# InkTime.net
KiCad netlist of a schematic drawn in EAGLE
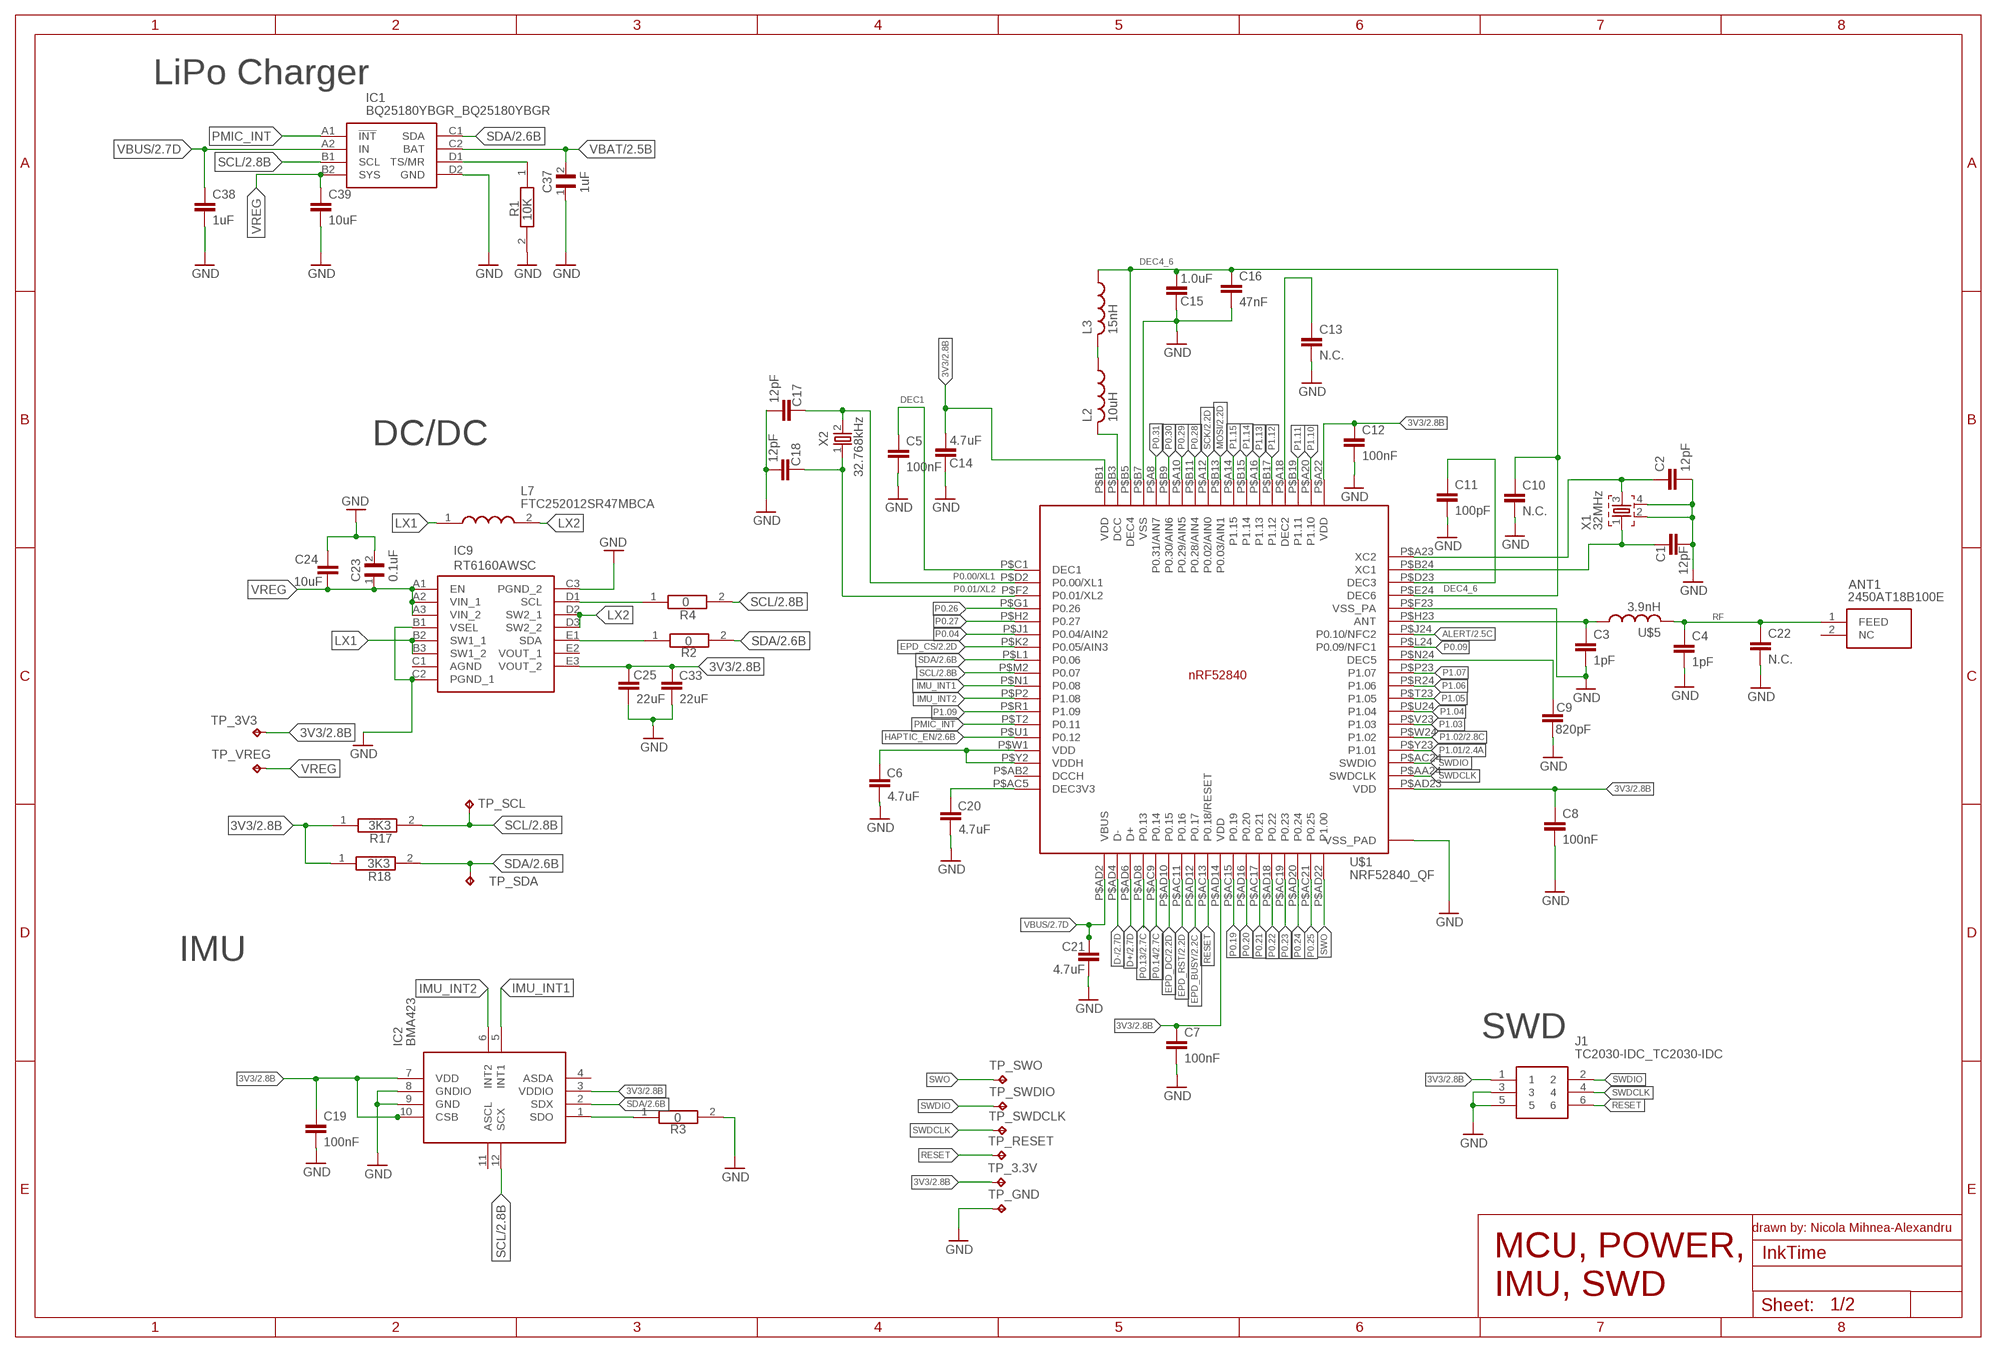
[diagram p0: schematic, sheet 1]
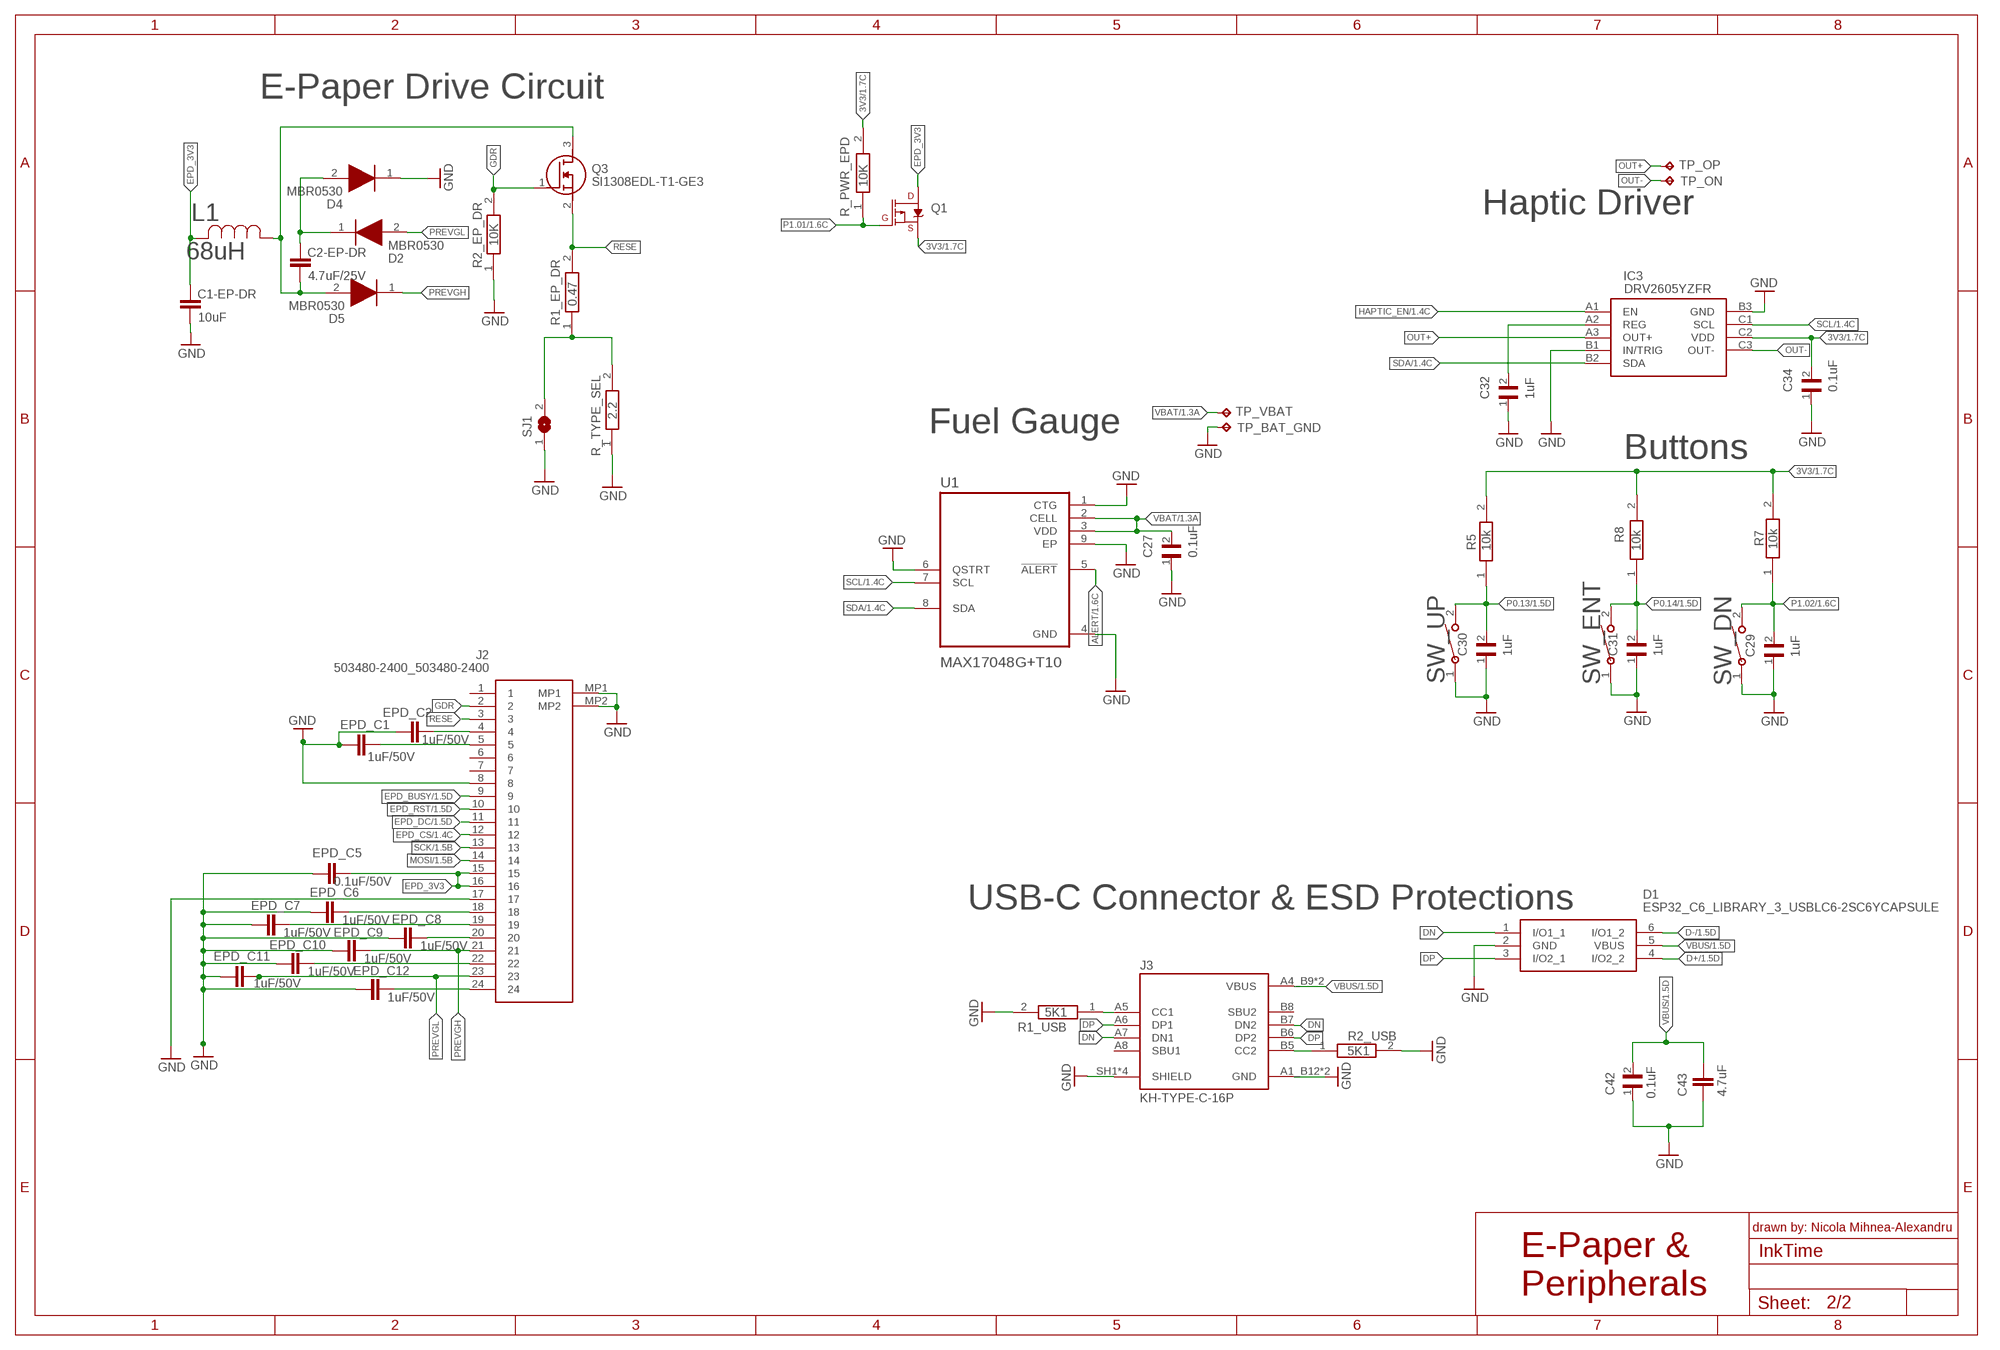
[diagram p1: schematic, sheet 2]

(export (version "E")
  (design (tool "Eeschema 10.0.6"))
  (components
    (comp (ref "C1-EP-DR")
      (value "10uF")
      (footprint "eagle-import:NORDIC_NRF_3_RESC0402_N")
      (libsource (lib "eagle-import") (part "NORDIC_NRF_3_CAPACITOR_0402_N"))
    )
    (comp (ref "C2-EP-DR")
      (value "4.7uF/25V")
      (footprint "eagle-import:NORDIC_NRF_3_RESC0402_N")
      (libsource (lib "eagle-import") (part "NORDIC_NRF_3_CAPACITOR_0402_N"))
    )
    (comp (ref "C27")
      (value "0.1uF")
      (footprint "eagle-import:GRM011R60J152KE01L_2_CAPC0201X13N")
      (libsource (lib "eagle-import") (part "GRM011R60J152KE01L_2_GRM011R60J152KE01LGRM"))
    )
    (comp (ref "C29")
      (value "1uF")
      (footprint "eagle-import:GRM011R60J152KE01L_2_CAPC0201X13N")
      (libsource (lib "eagle-import") (part "GRM011R60J152KE01L_2_GRM011R60J152KE01LGRM"))
    )
    (comp (ref "C30")
      (value "1uF")
      (footprint "eagle-import:GRM011R60J152KE01L_2_CAPC0201X13N")
      (libsource (lib "eagle-import") (part "GRM011R60J152KE01L_2_GRM011R60J152KE01LGRM"))
    )
    (comp (ref "C31")
      (value "1uF")
      (footprint "eagle-import:GRM011R60J152KE01L_2_CAPC0201X13N")
      (libsource (lib "eagle-import") (part "GRM011R60J152KE01L_2_GRM011R60J152KE01LGRM"))
    )
    (comp (ref "C32")
      (value "1uF")
      (footprint "eagle-import:GRM011R60J152KE01L_2_CAPC0201X13N")
      (libsource (lib "eagle-import") (part "GRM011R60J152KE01L_2_GRM011R60J152KE01LGRM"))
    )
    (comp (ref "C34")
      (value "0.1uF")
      (footprint "eagle-import:GRM011R60J152KE01L_2_CAPC0201X13N")
      (libsource (lib "eagle-import") (part "GRM011R60J152KE01L_2_GRM011R60J152KE01LGRM"))
    )
    (comp (ref "C42")
      (value "0.1uF")
      (footprint "eagle-import:GRM011R60J152KE01L_2_CAPC0201X13N")
      (fields (field (name "MF") "Murata") (field (name "MP") "GRM011R60J152KE01L"))
      (libsource (lib "eagle-import") (part "GRM011R60J152KE01L_2_GRM011R60J152KE01L"))
    )
    (comp (ref "C43")
      (value "4.7uF")
      (footprint "eagle-import:NORDIC_NRF_3_RESC0402_N")
      (libsource (lib "eagle-import") (part "NORDIC_NRF_3_CAPACITOR_0402_N"))
    )
    (comp (ref "D1")
      (value "ESP32_C6_LIBRARY_3_USBLC6-2SC6YCAPSULE")
      (footprint "eagle-import:ESP32_C6_LIBRARY_3_SOT95P280X145-6N")
      (libsource (lib "eagle-import") (part "ESP32_C6_LIBRARY_3_USBLC6-2SC6YCAPSULE"))
    )
    (comp (ref "D2")
      (value "MBR0530")
      (footprint "eagle-import:ESP32_C6_LIBRARY_5_SOD3716X135N")
      (libsource (lib "eagle-import") (part "ESP32_C6_LIBRARY_5_MBR0530MBRR"))
    )
    (comp (ref "D4")
      (value "MBR0530")
      (footprint "eagle-import:ESP32_C6_LIBRARY_5_SOD3716X135N")
      (libsource (lib "eagle-import") (part "ESP32_C6_LIBRARY_5_MBR0530MBRR"))
    )
    (comp (ref "D5")
      (value "MBR0530")
      (footprint "eagle-import:ESP32_C6_LIBRARY_5_SOD3716X135N")
      (libsource (lib "eagle-import") (part "ESP32_C6_LIBRARY_5_MBR0530MBRR"))
    )
    (comp (ref "EPD_C1")
      (value "1uF/50V")
      (footprint "eagle-import:NORDIC_NRF_3_RESC0402_N")
      (libsource (lib "eagle-import") (part "NORDIC_NRF_3_CAPACITOR_0402_N"))
    )
    (comp (ref "EPD_C2")
      (value "1uF/50V")
      (footprint "eagle-import:NORDIC_NRF_3_RESC0402_N")
      (libsource (lib "eagle-import") (part "NORDIC_NRF_3_CAPACITOR_0402_N"))
    )
    (comp (ref "EPD_C5")
      (value "0.1uF/50V")
      (footprint "eagle-import:NORDIC_NRF_3_RESC0402_N")
      (libsource (lib "eagle-import") (part "NORDIC_NRF_3_CAPACITOR_0402_N"))
    )
    (comp (ref "EPD_C6")
      (value "1uF/50V")
      (footprint "eagle-import:NORDIC_NRF_3_RESC0402_N")
      (libsource (lib "eagle-import") (part "NORDIC_NRF_3_CAPACITOR_0402_N"))
    )
    (comp (ref "EPD_C7")
      (value "1uF/50V")
      (footprint "eagle-import:NORDIC_NRF_3_RESC0402_N")
      (libsource (lib "eagle-import") (part "NORDIC_NRF_3_CAPACITOR_0402_N"))
    )
    (comp (ref "EPD_C8")
      (value "1uF/50V")
      (footprint "eagle-import:NORDIC_NRF_3_RESC0402_N")
      (libsource (lib "eagle-import") (part "NORDIC_NRF_3_CAPACITOR_0402_N"))
    )
    (comp (ref "EPD_C9")
      (value "1uF/50V")
      (footprint "eagle-import:NORDIC_NRF_3_RESC0402_N")
      (libsource (lib "eagle-import") (part "NORDIC_NRF_3_CAPACITOR_0402_N"))
    )
    (comp (ref "EPD_C10")
      (value "1uF/50V")
      (footprint "eagle-import:NORDIC_NRF_3_RESC0402_N")
      (libsource (lib "eagle-import") (part "NORDIC_NRF_3_CAPACITOR_0402_N"))
    )
    (comp (ref "EPD_C11")
      (value "1uF/50V")
      (footprint "eagle-import:NORDIC_NRF_3_RESC0402_N")
      (libsource (lib "eagle-import") (part "NORDIC_NRF_3_CAPACITOR_0402_N"))
    )
    (comp (ref "EPD_C12")
      (value "1uF/50V")
      (footprint "eagle-import:NORDIC_NRF_3_RESC0402_N")
      (libsource (lib "eagle-import") (part "NORDIC_NRF_3_CAPACITOR_0402_N"))
    )
    (comp (ref "IC3")
      (value "DRV2605YZFR")
      (footprint "eagle-import:DRV2605YZFR_BGA9C50P3X3_144X144X62")
      (libsource (lib "eagle-import") (part "DRV2605YZFR_DRV2605YZFR"))
    )
    (comp (ref "J2")
      (value "503480-2400_503480-2400")
      (footprint "eagle-import:503480-2400_5034802400")
      (fields
        (field (name "MANUFACTURER_PART_NUMBER") "503480-2400")
        (field (name "MOUSER_PART_NUMBER") "538-503480-2400")
      )
      (libsource (lib "eagle-import") (part "503480-2400_503480-2400"))
    )
    (comp (ref "J3")
      (value "KH-TYPE-C-16P")
      (footprint "eagle-import:KH-TYPE-C-16P_KINGHELM_KH-TYPE-C-16P")
      (libsource (lib "eagle-import") (part "KH-TYPE-C-16P_KH-TYPE-C-16PKH"))
    )
    (comp (ref "L1")
      (value "68uH")
      (footprint "eagle-import:ESP32_C6_LIBRARY_2_IND_4828-WE-TPC_WRE")
      (fields
        (field (name "MANUFACTURER_PART_NUMBER") "744043680")
        (field (name "COPYRIGHT") "Copyright (C) 2024 Ultra Librarian. All rights reserved.")
      )
      (libsource (lib "eagle-import") (part "ESP32_C6_LIBRARY_2_744043680IND_4828-WE-TPC_WRE"))
    )
    (comp (ref "Q1")
      (value "ESP32_C6_LIBRARY_4_ESP32_WROVER_SPARKFUN-DISCRETESEMI_MOSFET_PCH")
      (footprint "eagle-import:ESP32_C6_LIBRARY_4_ESP32_C6_LIBRARY_4_ESP32_C6_LIBRARY_4_ESP32_C6_LIBRARY_4_ESP32_WROVER_SPARKFUN-DISCRETESEMI_SOT23-3")
      (libsource (lib "eagle-import") (part "ESP32_C6_LIBRARY_4_ESP32_WROVER_SPARKFUN-DISCRETESEMI_MOSFET_PCH"))
    )
    (comp (ref "Q3")
      (value "SI1308EDL-T1-GE3")
      (footprint "eagle-import:ESP32_C6_LIBRARY_6_SOT65P210X110-3N")
      (libsource (lib "eagle-import") (part "ESP32_C6_LIBRARY_6_SI1308EDL-T1-GE3SIU"))
    )
    (comp (ref "R1_EP_DR")
      (value "0.47")
      (footprint "eagle-import:CPF0201D7K68C1_0201")
      (libsource (lib "eagle-import") (part "CPF0201D7K68C1_CPF0201D7K68C1"))
    )
    (comp (ref "R1_USB")
      (value "5K1")
      (footprint "eagle-import:CPF0201D7K68C1_0201")
      (libsource (lib "eagle-import") (part "CPF0201D7K68C1_CPF0201D7K68C1"))
    )
    (comp (ref "R2_EP_DR")
      (value "10K")
      (footprint "eagle-import:CPF0201D7K68C1_0201")
      (libsource (lib "eagle-import") (part "CPF0201D7K68C1_CPF0201D7K68C1"))
    )
    (comp (ref "R2_USB")
      (value "5K1")
      (footprint "eagle-import:CPF0201D7K68C1_0201")
      (libsource (lib "eagle-import") (part "CPF0201D7K68C1_CPF0201D7K68C1"))
    )
    (comp (ref "R5")
      (value "10k")
      (footprint "eagle-import:CPF0201D7K68C1_0201")
      (libsource (lib "eagle-import") (part "CPF0201D7K68C1_CPF0201D7K68C1"))
    )
    (comp (ref "R7")
      (value "10k")
      (footprint "eagle-import:CPF0201D7K68C1_0201")
      (libsource (lib "eagle-import") (part "CPF0201D7K68C1_CPF0201D7K68C1"))
    )
    (comp (ref "R8")
      (value "10k")
      (footprint "eagle-import:CPF0201D7K68C1_0201")
      (libsource (lib "eagle-import") (part "CPF0201D7K68C1_CPF0201D7K68C1"))
    )
    (comp (ref "R_PWR_EPD")
      (value "10K")
      (footprint "eagle-import:CPF0201D7K68C1_0201")
      (libsource (lib "eagle-import") (part "CPF0201D7K68C1_CPF0201D7K68C1"))
    )
    (comp (ref "R_TYPE_SEL")
      (value "2.2")
      (footprint "eagle-import:CPF0201D7K68C1_0201")
      (libsource (lib "eagle-import") (part "CPF0201D7K68C1_CPF0201D7K68C1"))
    )
    (comp (ref "SJ1")
      (value "ESP32_C6_LIBRARY_7_JUMPER_SJ")
      (footprint "eagle-import:ESP32_C6_LIBRARY_7_JUMPER_SJ")
      (libsource (lib "eagle-import") (part "ESP32_C6_LIBRARY_7_JUMPER_SJ"))
    )
    (comp (ref "SW_DN")
      (value "2025-10-22_07-23-44_LIBRARY_EVP-AKE31A")
      (footprint "eagle-import:2025-10-22_07-23-44_LIBRARY_SW_EVP-AKE31A_PAN")
      (libsource (lib "eagle-import") (part "2025-10-22_07-23-44_LIBRARY_EVP-AKE31A"))
    )
    (comp (ref "SW_ENT")
      (value "2025-10-22_07-23-44_LIBRARY_EVP-AKE31A")
      (footprint "eagle-import:2025-10-22_07-23-44_LIBRARY_SW_EVP-AKE31A_PAN")
      (libsource (lib "eagle-import") (part "2025-10-22_07-23-44_LIBRARY_EVP-AKE31A"))
    )
    (comp (ref "SW_UP")
      (value "2025-10-22_07-23-44_LIBRARY_EVP-AKE31A")
      (footprint "eagle-import:2025-10-22_07-23-44_LIBRARY_SW_EVP-AKE31A_PAN")
      (libsource (lib "eagle-import") (part "2025-10-22_07-23-44_LIBRARY_EVP-AKE31A"))
    )
    (comp (ref "TP_BAT_GND")
      (value "HECTOR_WATCH_1_TPTP20R")
      (footprint "eagle-import:HECTOR_WATCH_1_TP20R")
      (libsource (lib "eagle-import") (part "HECTOR_WATCH_1_TPTP20R"))
    )
    (comp (ref "TP_ON")
      (value "HECTOR_WATCH_1_TPTP20R")
      (footprint "eagle-import:HECTOR_WATCH_1_TP20R")
      (libsource (lib "eagle-import") (part "HECTOR_WATCH_1_TPTP20R"))
    )
    (comp (ref "TP_OP")
      (value "HECTOR_WATCH_1_TPTP20R")
      (footprint "eagle-import:HECTOR_WATCH_1_TP20R")
      (libsource (lib "eagle-import") (part "HECTOR_WATCH_1_TPTP20R"))
    )
    (comp (ref "TP_VBAT")
      (value "HECTOR_WATCH_1_TPTP20R")
      (footprint "eagle-import:HECTOR_WATCH_1_TP20R")
      (libsource (lib "eagle-import") (part "HECTOR_WATCH_1_TPTP20R"))
    )
    (comp (ref "U1")
      (value "MAX17048G+T10")
      (footprint "eagle-import:ESP32_C6_LIBRARY_SON50P200X200X80-9N")
      (fields (field (name "MF") "Analog Devices"))
      (libsource (lib "eagle-import") (part "ESP32_C6_LIBRARY_MAX17048G+T10"))
    )
    (comp (ref "ANT1")
      (value "2450AT18B100E")
      (footprint "eagle-import:2450AT18B100E_ANTC3216X140N")
      (fields (field (name "MOUSER_PART_NUMBER") "609-2450AT18B100E"))
      (libsource (lib "eagle-import") (part "2450AT18B100E_2450AT18B100E"))
    )
    (comp (ref "C1")
      (value "12pF")
      (footprint "eagle-import:NORDIC_NRF_3_RESC0201_N")
      (libsource (lib "eagle-import") (part "NORDIC_NRF_3_CAPACITOR_0201_N"))
    )
    (comp (ref "C2")
      (value "12pF")
      (footprint "eagle-import:NORDIC_NRF_3_RESC0201_N")
      (libsource (lib "eagle-import") (part "NORDIC_NRF_3_CAPACITOR_0201_N"))
    )
    (comp (ref "C3")
      (value "1pF")
      (footprint "eagle-import:NORDIC_NRF_3_RESC0201_N")
      (libsource (lib "eagle-import") (part "NORDIC_NRF_3_CAPACITOR_0201_N"))
    )
    (comp (ref "C4")
      (value "1pF")
      (footprint "eagle-import:NORDIC_NRF_3_RESC0201_N")
      (libsource (lib "eagle-import") (part "NORDIC_NRF_3_CAPACITOR_0201_N"))
    )
    (comp (ref "C5")
      (value "100nF")
      (footprint "eagle-import:NORDIC_NRF_3_RESC0201_N")
      (libsource (lib "eagle-import") (part "NORDIC_NRF_3_CAPACITOR_0201_N"))
    )
    (comp (ref "C6")
      (value "4.7uF")
      (footprint "eagle-import:NORDIC_NRF_3_RESC0402_N")
      (libsource (lib "eagle-import") (part "NORDIC_NRF_3_CAPACITOR_0402_N"))
    )
    (comp (ref "C7")
      (value "100nF")
      (footprint "eagle-import:NORDIC_NRF_3_RESC0201_N")
      (libsource (lib "eagle-import") (part "NORDIC_NRF_3_CAPACITOR_0201_N"))
    )
    (comp (ref "C8")
      (value "100nF")
      (footprint "eagle-import:NORDIC_NRF_3_RESC0201_N")
      (libsource (lib "eagle-import") (part "NORDIC_NRF_3_CAPACITOR_0201_N"))
    )
    (comp (ref "C9")
      (value "820pF")
      (footprint "eagle-import:NORDIC_NRF_3_RESC0201_N")
      (libsource (lib "eagle-import") (part "NORDIC_NRF_3_CAPACITOR_0201_N"))
    )
    (comp (ref "C10")
      (value "N.C.")
      (footprint "eagle-import:NORDIC_NRF_3_RESC0201_N")
      (libsource (lib "eagle-import") (part "NORDIC_NRF_3_CAPACITOR_0201_N"))
    )
    (comp (ref "C11")
      (value "100pF")
      (footprint "eagle-import:NORDIC_NRF_3_RESC0201_N")
      (libsource (lib "eagle-import") (part "NORDIC_NRF_3_CAPACITOR_0201_N"))
    )
    (comp (ref "C12")
      (value "100nF")
      (footprint "eagle-import:NORDIC_NRF_3_RESC0201_N")
      (libsource (lib "eagle-import") (part "NORDIC_NRF_3_CAPACITOR_0201_N"))
    )
    (comp (ref "C13")
      (value "N.C.")
      (footprint "eagle-import:NORDIC_NRF_3_RESC0201_N")
      (libsource (lib "eagle-import") (part "NORDIC_NRF_3_CAPACITOR_0201_N"))
    )
    (comp (ref "C14")
      (value "4.7uF")
      (footprint "eagle-import:NORDIC_NRF_3_RESC0402_N")
      (libsource (lib "eagle-import") (part "NORDIC_NRF_3_CAPACITOR_0402_N"))
    )
    (comp (ref "C15")
      (value "1.0uF")
      (footprint "eagle-import:NORDIC_NRF_3_RESC0402_N")
      (libsource (lib "eagle-import") (part "NORDIC_NRF_3_CAPACITOR_0402_N"))
    )
    (comp (ref "C16")
      (value "47nF")
      (footprint "eagle-import:NORDIC_NRF_3_RESC0201_N")
      (libsource (lib "eagle-import") (part "NORDIC_NRF_3_CAPACITOR_0201_N"))
    )
    (comp (ref "C17")
      (value "12pF")
      (footprint "eagle-import:NORDIC_NRF_3_RESC0201_N")
      (libsource (lib "eagle-import") (part "NORDIC_NRF_3_CAPACITOR_0201_N"))
    )
    (comp (ref "C18")
      (value "12pF")
      (footprint "eagle-import:NORDIC_NRF_3_RESC0201_N")
      (libsource (lib "eagle-import") (part "NORDIC_NRF_3_CAPACITOR_0201_N"))
    )
    (comp (ref "C19")
      (value "100nF")
      (footprint "eagle-import:NORDIC_NRF_3_RESC0201_N")
      (libsource (lib "eagle-import") (part "NORDIC_NRF_3_CAPACITOR_0201_N"))
    )
    (comp (ref "C20")
      (value "4.7uF")
      (footprint "eagle-import:NORDIC_NRF_3_RESC0402_N")
      (libsource (lib "eagle-import") (part "NORDIC_NRF_3_CAPACITOR_0402_N"))
    )
    (comp (ref "C21")
      (value "4.7uF")
      (footprint "eagle-import:NORDIC_NRF_3_RESC0402_N")
      (libsource (lib "eagle-import") (part "NORDIC_NRF_3_CAPACITOR_0402_N"))
    )
    (comp (ref "C22")
      (value "N.C.")
      (footprint "eagle-import:NORDIC_NRF_3_RESC0201_N")
      (libsource (lib "eagle-import") (part "NORDIC_NRF_3_CAPACITOR_0201_N"))
    )
    (comp (ref "C23")
      (value "0.1uF")
      (footprint "eagle-import:GRM011R60J152KE01L_2_CAPC0201X13N")
      (libsource (lib "eagle-import") (part "GRM011R60J152KE01L_2_GRM011R60J152KE01LGRM"))
    )
    (comp (ref "C24")
      (value "10uF")
      (footprint "eagle-import:NORDIC_NRF_3_RESC0402_N")
      (libsource (lib "eagle-import") (part "NORDIC_NRF_3_CAPACITOR_0402_N"))
    )
    (comp (ref "C25")
      (value "22uF")
      (footprint "eagle-import:NORDIC_NRF_3_RESC0402_N")
      (libsource (lib "eagle-import") (part "NORDIC_NRF_3_CAPACITOR_0402_N"))
    )
    (comp (ref "C33")
      (value "22uF")
      (footprint "eagle-import:NORDIC_NRF_3_RESC0402_N")
      (libsource (lib "eagle-import") (part "NORDIC_NRF_3_CAPACITOR_0402_N"))
    )
    (comp (ref "C37")
      (value "1uF")
      (footprint "eagle-import:GRM011R60J152KE01L_2_CAPC0201X13N")
      (libsource (lib "eagle-import") (part "GRM011R60J152KE01L_2_GRM011R60J152KE01LGRM"))
    )
    (comp (ref "C38")
      (value "1uF")
      (footprint "eagle-import:NORDIC_NRF_3_RESC0402_N")
      (libsource (lib "eagle-import") (part "NORDIC_NRF_3_CAPACITOR_0402_N"))
    )
    (comp (ref "C39")
      (value "10uF")
      (footprint "eagle-import:NORDIC_NRF_3_RESC0402_N")
      (libsource (lib "eagle-import") (part "NORDIC_NRF_3_CAPACITOR_0402_N"))
    )
    (comp (ref "IC1")
      (value "BQ25180YBGR_BQ25180YBGR")
      (footprint "eagle-import:BQ25180YBGR_BGA8C40P2X4_100X155X50")
      (fields
        (field (name "ARROW_PART_NUMBER") "BQ25180YBGR")
        (field (name "MOUSER_PART_NUMBER") "595-BQ25180YBGR")
      )
      (libsource (lib "eagle-import") (part "BQ25180YBGR_BQ25180YBGR"))
    )
    (comp (ref "IC2")
      (value "BMA423")
      (footprint "eagle-import:BMA423_BMA423")
      (fields (field (name "MOUSER_PART_NUMBER") "262-BMA423"))
      (libsource (lib "eagle-import") (part "BMA423_BMA423"))
    )
    (comp (ref "IC9")
      (value "RT6160AWSC")
      (footprint "eagle-import:RT6160AWSC_BGA15C40P3X5_140X230X60")
      (fields (field (name "MOUSER_PART_NUMBER") "835-RT6160AWSC"))
      (libsource (lib "eagle-import") (part "RT6160AWSC_RT6160AWSC"))
    )
    (comp (ref "J1")
      (value "TC2030-IDC_TC2030-IDC")
      (footprint "eagle-import:TC2030-IDC_TC2030IDC")
      (fields (field (name "MANUFACTURER_PART_NUMBER") "TC2030-IDC"))
      (libsource (lib "eagle-import") (part "TC2030-IDC_TC2030-IDC"))
    )
    (comp (ref "L2")
      (value "10uH")
      (footprint "eagle-import:NORDIC_NRF_2_RESC0201_N")
      (libsource (lib "eagle-import") (part "NORDIC_NRF_2_INDUCTOR_0201_N"))
    )
    (comp (ref "L3")
      (value "15nH")
      (footprint "eagle-import:NORDIC_NRF_2_RESC0201_N")
      (libsource (lib "eagle-import") (part "NORDIC_NRF_2_INDUCTOR_0201_N"))
    )
    (comp (ref "L7")
      (value "FTC252012SR47MBCA")
      (footprint "eagle-import:MLP2016SR47MT0S1_INDC2016X100N")
      (libsource (lib "eagle-import") (part "MLP2016SR47MT0S1_FTC252012SR47MBCA"))
    )
    (comp (ref "R1")
      (value "10K")
      (footprint "eagle-import:CPF0201D7K68C1_0201")
      (libsource (lib "eagle-import") (part "CPF0201D7K68C1_CPF0201D7K68C1"))
    )
    (comp (ref "R2")
      (value "0")
      (footprint "eagle-import:CPF0201D7K68C1_0201")
      (libsource (lib "eagle-import") (part "CPF0201D7K68C1_CPF0201D7K68C1"))
    )
    (comp (ref "R3")
      (value "0")
      (footprint "eagle-import:CPF0201D7K68C1_0201")
      (libsource (lib "eagle-import") (part "CPF0201D7K68C1_CPF0201D7K68C1"))
    )
    (comp (ref "R4")
      (value "0")
      (footprint "eagle-import:CPF0201D7K68C1_0201")
      (libsource (lib "eagle-import") (part "CPF0201D7K68C1_CPF0201D7K68C1"))
    )
    (comp (ref "R17")
      (value "3K3")
      (footprint "eagle-import:CPF0201D7K68C1_0201")
      (libsource (lib "eagle-import") (part "CPF0201D7K68C1_CPF0201D7K68C1"))
    )
    (comp (ref "R18")
      (value "3K3")
      (footprint "eagle-import:CPF0201D7K68C1_0201")
      (libsource (lib "eagle-import") (part "CPF0201D7K68C1_CPF0201D7K68C1"))
    )
    (comp (ref "TP_3.3V")
      (value "HECTOR_WATCH_1_TPTP20R")
      (footprint "eagle-import:HECTOR_WATCH_1_TP20R")
      (libsource (lib "eagle-import") (part "HECTOR_WATCH_1_TPTP20R"))
    )
    (comp (ref "TP_3V3")
      (value "HECTOR_WATCH_1_TPTP20R")
      (footprint "eagle-import:HECTOR_WATCH_1_TP20R")
      (libsource (lib "eagle-import") (part "HECTOR_WATCH_1_TPTP20R"))
    )
    (comp (ref "TP_GND")
      (value "HECTOR_WATCH_1_TPTP20R")
      (footprint "eagle-import:HECTOR_WATCH_1_TP20R")
      (libsource (lib "eagle-import") (part "HECTOR_WATCH_1_TPTP20R"))
    )
    (comp (ref "TP_RESET")
      (value "HECTOR_WATCH_1_TPTP20R")
      (footprint "eagle-import:HECTOR_WATCH_1_TP20R")
      (libsource (lib "eagle-import") (part "HECTOR_WATCH_1_TPTP20R"))
    )
    (comp (ref "TP_SCL")
      (value "HECTOR_WATCH_1_TPTP20R")
      (footprint "eagle-import:HECTOR_WATCH_1_TP20R")
      (libsource (lib "eagle-import") (part "HECTOR_WATCH_1_TPTP20R"))
    )
    (comp (ref "TP_SDA")
      (value "HECTOR_WATCH_1_TPTP20R")
      (footprint "eagle-import:HECTOR_WATCH_1_TP20R")
      (libsource (lib "eagle-import") (part "HECTOR_WATCH_1_TPTP20R"))
    )
    (comp (ref "TP_SWDCLK")
      (value "HECTOR_WATCH_1_TPTP20R")
      (footprint "eagle-import:HECTOR_WATCH_1_TP20R")
      (libsource (lib "eagle-import") (part "HECTOR_WATCH_1_TPTP20R"))
    )
    (comp (ref "TP_SWDIO")
      (value "HECTOR_WATCH_1_TPTP20R")
      (footprint "eagle-import:HECTOR_WATCH_1_TP20R")
      (libsource (lib "eagle-import") (part "HECTOR_WATCH_1_TPTP20R"))
    )
    (comp (ref "TP_SWO")
      (value "HECTOR_WATCH_1_TPTP20R")
      (footprint "eagle-import:HECTOR_WATCH_1_TP20R")
      (libsource (lib "eagle-import") (part "HECTOR_WATCH_1_TPTP20R"))
    )
    (comp (ref "TP_VREG")
      (value "HECTOR_WATCH_1_TPTP20R")
      (footprint "eagle-import:HECTOR_WATCH_1_TP20R")
      (libsource (lib "eagle-import") (part "HECTOR_WATCH_1_TPTP20R"))
    )
    (comp (ref "U$1")
      (value "NRF52840_QF")
      (footprint "eagle-import:NORDIC_NRF_4_AQFN50P700X700X85_HS-74N")
      (libsource (lib "eagle-import") (part "NORDIC_NRF_4_NRF52840_QF"))
    )
    (comp (ref "U$5")
      (value "3.9nH")
      (footprint "eagle-import:NORDIC_NRF_2_RESC0201_N")
      (libsource (lib "eagle-import") (part "NORDIC_NRF_2_INDUCTOR_0201_N"))
    )
    (comp (ref "X1")
      (value "32MHz")
      (footprint "eagle-import:NORDIC_NRF_BT-XTAL_2016_N")
      (libsource (lib "eagle-import") (part "NORDIC_NRF_XTAL_32MHZ"))
    )
    (comp (ref "X2")
      (value "32.768kHz")
      (footprint "eagle-import:NORDIC_NRF_1_XTAL_3215_N")
      (libsource (lib "eagle-import") (part "NORDIC_NRF_1_XTAL_32KHZ"))
    )
  )
  (nets
    (net (code "1") (name "3V3") (class "Default")
      (node (ref "C12") (pin "1") (pinfunction "1_1") (pintype "passive"))
      (node (ref "C14") (pin "2") (pinfunction "2_2") (pintype "passive"))
      (node (ref "C19") (pin "1") (pinfunction "1_1") (pintype "passive"))
      (node (ref "C25") (pin "1") (pinfunction "1_1") (pintype "passive"))
      (node (ref "C33") (pin "1") (pinfunction "1_1") (pintype "passive"))
      (node (ref "C34") (pin "2") (pinfunction "2_2") (pintype "passive"))
      (node (ref "C7") (pin "1") (pinfunction "1_1") (pintype "passive"))
      (node (ref "C8") (pin "1") (pinfunction "1_1") (pintype "passive"))
      (node (ref "IC2") (pin "3") (pinfunction "VDDIO_3") (pintype "bidirectional"))
      (node (ref "IC3") (pin "C2") (pinfunction "VDD_C2") (pintype "bidirectional"))
      (node (ref "IC9") (pin "E3") (pinfunction "VOUT_2_E3") (pintype "bidirectional"))
      (node (ref "J1") (pin "1") (pinfunction "1_1") (pintype "bidirectional"))
      (node (ref "Q1") (pin "2") (pinfunction "S_2") (pintype "bidirectional"))
      (node (ref "R17") (pin "1") (pinfunction "1_1") (pintype "bidirectional"))
      (node (ref "R18") (pin "1") (pinfunction "1_1") (pintype "bidirectional"))
      (node (ref "R5") (pin "2") (pinfunction "2_2") (pintype "bidirectional"))
      (node (ref "R7") (pin "2") (pinfunction "2_2") (pintype "bidirectional"))
      (node (ref "R8") (pin "2") (pinfunction "2_2") (pintype "bidirectional"))
      (node (ref "R_PWR_EPD") (pin "2") (pinfunction "2_2") (pintype "bidirectional"))
      (node (ref "TP_3.3V") (pin "TP") (pinfunction "TP_TP") (pintype "input"))
      (node (ref "TP_3V3") (pin "TP") (pinfunction "TP_TP") (pintype "input"))
      (node (ref "U$1") (pin "P$A22") (pinfunction "VDD_P$A22") (pintype "power_in"))
      (node (ref "U$1") (pin "P$AD14") (pinfunction "VDD_P$AD14") (pintype "power_in"))
      (node (ref "U$1") (pin "P$AD23") (pinfunction "VDD_P$AD23") (pintype "power_in"))
      (node (ref "U$1") (pin "P$B1") (pinfunction "VDD_P$B1") (pintype "power_in"))
    )
    (net (code "2") (name "ALERT") (class "Default")
      (node (ref "U$1") (pin "P$J24") (pinfunction "P0.10/NFC2_P$J24") (pintype "bidirectional"))
      (node (ref "U1") (pin "5") (pinfunction "~{ALERT}_5") (pintype "output"))
    )
    (net (code "3") (name "D+") (class "Default")
      (node (ref "D1") (pin "4") (pinfunction "I/O2_2_4") (pintype "bidirectional"))
      (node (ref "U$1") (pin "P$AD6") (pinfunction "D+_P$AD6") (pintype "bidirectional"))
    )
    (net (code "4") (name "D-") (class "Default")
      (node (ref "D1") (pin "6") (pinfunction "I/O1_2_6") (pintype "bidirectional"))
      (node (ref "U$1") (pin "P$AD4") (pinfunction "D-_P$AD4") (pintype "bidirectional"))
    )
    (net (code "5") (name "DEC1") (class "Default")
      (node (ref "C5") (pin "1") (pinfunction "1_1") (pintype "passive"))
      (node (ref "U$1") (pin "P$C1") (pinfunction "DEC1_P$C1") (pintype "power_in"))
    )
    (net (code "6") (name "DEC4_6") (class "Default")
      (node (ref "C10") (pin "1") (pinfunction "1_1") (pintype "passive"))
      (node (ref "C15") (pin "2") (pinfunction "2_2") (pintype "passive"))
      (node (ref "C16") (pin "1") (pinfunction "1_1") (pintype "passive"))
      (node (ref "L3") (pin "1") (pinfunction "1_1") (pintype "passive"))
      (node (ref "U$1") (pin "P$B5") (pinfunction "DEC4_P$B5") (pintype "power_in"))
      (node (ref "U$1") (pin "P$E24") (pinfunction "DEC6_P$E24") (pintype "bidirectional"))
    )
    (net (code "7") (name "DN") (class "Default")
      (node (ref "D1") (pin "1") (pinfunction "I/O1_1_1") (pintype "bidirectional"))
      (node (ref "J3") (pin "A7") (pinfunction "DN1_A7") (pintype "bidirectional"))
      (node (ref "J3") (pin "B7") (pinfunction "DN2_B7") (pintype "bidirectional"))
    )
    (net (code "8") (name "DP") (class "Default")
      (node (ref "D1") (pin "3") (pinfunction "I/O2_1_3") (pintype "bidirectional"))
      (node (ref "J3") (pin "A6") (pinfunction "DP1_A6") (pintype "bidirectional"))
      (node (ref "J3") (pin "B6") (pinfunction "DP2_B6") (pintype "bidirectional"))
    )
    (net (code "9") (name "EPD_3V3") (class "Default")
      (node (ref "C1-EP-DR") (pin "1") (pinfunction "1_1") (pintype "passive"))
      (node (ref "EPD_C5") (pin "2") (pinfunction "2_2") (pintype "passive"))
      (node (ref "J2") (pin "15") (pinfunction "15_15") (pintype "bidirectional"))
      (node (ref "J2") (pin "16") (pinfunction "16_16") (pintype "bidirectional"))
      (node (ref "L1") (pin "2") (pinfunction "2_2") (pintype "passive"))
      (node (ref "Q1") (pin "3") (pinfunction "D_3") (pintype "bidirectional"))
    )
    (net (code "10") (name "EPD_BUSY") (class "Default")
      (node (ref "J2") (pin "9") (pinfunction "9_9") (pintype "bidirectional"))
      (node (ref "U$1") (pin "P$AD12") (pinfunction "P0.17_P$AD12") (pintype "bidirectional"))
    )
    (net (code "11") (name "EPD_CS") (class "Default")
      (node (ref "J2") (pin "12") (pinfunction "12_12") (pintype "bidirectional"))
      (node (ref "U$1") (pin "P$K2") (pinfunction "P0.05/AIN3_P$K2") (pintype "bidirectional"))
    )
    (net (code "12") (name "EPD_DC") (class "Default")
      (node (ref "J2") (pin "11") (pinfunction "11_11") (pintype "bidirectional"))
      (node (ref "U$1") (pin "P$AD10") (pinfunction "P0.15_P$AD10") (pintype "bidirectional"))
    )
    (net (code "13") (name "EPD_RST") (class "Default")
      (node (ref "J2") (pin "10") (pinfunction "10_10") (pintype "bidirectional"))
      (node (ref "U$1") (pin "P$AC11") (pinfunction "P0.16_P$AC11") (pintype "bidirectional"))
    )
    (net (code "14") (name "GDR") (class "Default")
      (node (ref "J2") (pin "2") (pinfunction "2_2") (pintype "bidirectional"))
      (node (ref "Q3") (pin "1") (pinfunction "G_1") (pintype "bidirectional"))
      (node (ref "R2_EP_DR") (pin "2") (pinfunction "2_2") (pintype "bidirectional"))
    )
    (net (code "15") (name "GND") (class "Default")
      (node (ref "C1") (pin "2") (pinfunction "2_2") (pintype "passive"))
      (node (ref "C1-EP-DR") (pin "2") (pinfunction "2_2") (pintype "passive"))
      (node (ref "C10") (pin "2") (pinfunction "2_2") (pintype "passive"))
      (node (ref "C11") (pin "2") (pinfunction "2_2") (pintype "passive"))
      (node (ref "C12") (pin "2") (pinfunction "2_2") (pintype "passive"))
      (node (ref "C13") (pin "2") (pinfunction "2_2") (pintype "passive"))
      (node (ref "C14") (pin "1") (pinfunction "1_1") (pintype "passive"))
      (node (ref "C15") (pin "1") (pinfunction "1_1") (pintype "passive"))
      (node (ref "C16") (pin "2") (pinfunction "2_2") (pintype "passive"))
      (node (ref "C17") (pin "2") (pinfunction "2_2") (pintype "passive"))
      (node (ref "C18") (pin "2") (pinfunction "2_2") (pintype "passive"))
      (node (ref "C19") (pin "2") (pinfunction "2_2") (pintype "passive"))
      (node (ref "C2") (pin "2") (pinfunction "2_2") (pintype "passive"))
      (node (ref "C20") (pin "2") (pinfunction "2_2") (pintype "passive"))
      (node (ref "C21") (pin "2") (pinfunction "2_2") (pintype "passive"))
      (node (ref "C22") (pin "2") (pinfunction "2_2") (pintype "passive"))
      (node (ref "C23") (pin "2") (pinfunction "2_2") (pintype "passive"))
      (node (ref "C24") (pin "1") (pinfunction "1_1") (pintype "passive"))
      (node (ref "C25") (pin "2") (pinfunction "2_2") (pintype "passive"))
      (node (ref "C27") (pin "1") (pinfunction "1_1") (pintype "passive"))
      (node (ref "C29") (pin "1") (pinfunction "1_1") (pintype "passive"))
      (node (ref "C3") (pin "2") (pinfunction "2_2") (pintype "passive"))
      (node (ref "C30") (pin "1") (pinfunction "1_1") (pintype "passive"))
      (node (ref "C31") (pin "1") (pinfunction "1_1") (pintype "passive"))
      (node (ref "C32") (pin "1") (pinfunction "1_1") (pintype "passive"))
      (node (ref "C33") (pin "2") (pinfunction "2_2") (pintype "passive"))
      (node (ref "C34") (pin "1") (pinfunction "1_1") (pintype "passive"))
      (node (ref "C37") (pin "1") (pinfunction "1_1") (pintype "passive"))
      (node (ref "C38") (pin "2") (pinfunction "2_2") (pintype "passive"))
      (node (ref "C39") (pin "2") (pinfunction "2_2") (pintype "passive"))
      (node (ref "C4") (pin "2") (pinfunction "2_2") (pintype "passive"))
      (node (ref "C42") (pin "1") (pinfunction "1_1") (pintype "passive"))
      (node (ref "C43") (pin "1") (pinfunction "1_1") (pintype "passive"))
      (node (ref "C5") (pin "2") (pinfunction "2_2") (pintype "passive"))
      (node (ref "C6") (pin "2") (pinfunction "2_2") (pintype "passive"))
      (node (ref "C7") (pin "2") (pinfunction "2_2") (pintype "passive"))
      (node (ref "C8") (pin "2") (pinfunction "2_2") (pintype "passive"))
      (node (ref "C9") (pin "2") (pinfunction "2_2") (pintype "passive"))
      (node (ref "D1") (pin "2") (pinfunction "GND_2") (pintype "bidirectional"))
      (node (ref "D4") (pin "1") (pinfunction "K_1") (pintype "bidirectional"))
      (node (ref "EPD_C1") (pin "1") (pinfunction "1_1") (pintype "passive"))
      (node (ref "EPD_C10") (pin "1") (pinfunction "1_1") (pintype "passive"))
      (node (ref "EPD_C11") (pin "1") (pinfunction "1_1") (pintype "passive"))
      (node (ref "EPD_C12") (pin "1") (pinfunction "1_1") (pintype "passive"))
      (node (ref "EPD_C2") (pin "1") (pinfunction "1_1") (pintype "passive"))
      (node (ref "EPD_C5") (pin "1") (pinfunction "1_1") (pintype "passive"))
      (node (ref "EPD_C6") (pin "1") (pinfunction "1_1") (pintype "passive"))
      (node (ref "EPD_C7") (pin "1") (pinfunction "1_1") (pintype "passive"))
      (node (ref "EPD_C8") (pin "1") (pinfunction "1_1") (pintype "passive"))
      (node (ref "EPD_C9") (pin "1") (pinfunction "1_1") (pintype "passive"))
      (node (ref "IC1") (pin "D2") (pinfunction "GND_D2") (pintype "bidirectional"))
      (node (ref "IC2") (pin "8") (pinfunction "GNDIO_8") (pintype "bidirectional"))
      (node (ref "IC2") (pin "9") (pinfunction "GND_9") (pintype "bidirectional"))
      (node (ref "IC3") (pin "B1") (pinfunction "IN/TRIG_B1") (pintype "bidirectional"))
      (node (ref "IC3") (pin "B3") (pinfunction "GND_B3") (pintype "bidirectional"))
      (node (ref "IC9") (pin "B1") (pinfunction "VSEL_B1") (pintype "bidirectional"))
      (node (ref "IC9") (pin "C2") (pinfunction "PGND_1_C2") (pintype "bidirectional"))
      (node (ref "IC9") (pin "C3") (pinfunction "PGND_2_C3") (pintype "bidirectional"))
      (node (ref "J1") (pin "3") (pinfunction "3_3") (pintype "bidirectional"))
      (node (ref "J1") (pin "5") (pinfunction "5_5") (pintype "bidirectional"))
      (node (ref "J2") (pin "17") (pinfunction "17_17") (pintype "bidirectional"))
      (node (ref "J2") (pin "8") (pinfunction "8_8") (pintype "bidirectional"))
      (node (ref "J2") (pin "MP1") (pinfunction "MP1_MP1") (pintype "bidirectional"))
      (node (ref "J2") (pin "MP2") (pinfunction "MP2_MP2") (pintype "bidirectional"))
      (node (ref "J3") (pin "A12_B1") (pinfunction "GND_A12_B1") (pintype "power_in"))
      (node (ref "J3") (pin "A1_B12") (pinfunction "GND_A1_B12") (pintype "power_in"))
      (node (ref "J3") (pin "SH1") (pinfunction "SHIELD_SH1") (pintype "passive"))
      (node (ref "J3") (pin "SH2") (pinfunction "SHIELD_SH2") (pintype "passive"))
      (node (ref "J3") (pin "SH3") (pinfunction "SHIELD_SH3") (pintype "passive"))
      (node (ref "J3") (pin "SH4") (pinfunction "SHIELD_SH4") (pintype "passive"))
      (node (ref "R1") (pin "2") (pinfunction "2_2") (pintype "bidirectional"))
      (node (ref "R1_USB") (pin "2") (pinfunction "2_2") (pintype "bidirectional"))
      (node (ref "R2_EP_DR") (pin "1") (pinfunction "1_1") (pintype "bidirectional"))
      (node (ref "R2_USB") (pin "2") (pinfunction "2_2") (pintype "bidirectional"))
      (node (ref "R3") (pin "2") (pinfunction "2_2") (pintype "bidirectional"))
      (node (ref "R_TYPE_SEL") (pin "1") (pinfunction "1_1") (pintype "bidirectional"))
      (node (ref "SJ1") (pin "1") (pinfunction "1_1") (pintype "passive"))
      (node (ref "SW_DN") (pin "1") (pinfunction "1_1") (pintype "passive"))
      (node (ref "SW_ENT") (pin "1") (pinfunction "1_1") (pintype "passive"))
      (node (ref "SW_UP") (pin "1") (pinfunction "1_1") (pintype "passive"))
      (node (ref "TP_BAT_GND") (pin "TP") (pinfunction "TP_TP") (pintype "input"))
      (node (ref "TP_GND") (pin "TP") (pinfunction "TP_TP") (pintype "input"))
      (node (ref "U$1") (pin "P$74") (pinfunction "VSS_PAD_P$74") (pintype "bidirectional"))
      (node (ref "U$1") (pin "P$75") (pinfunction "VSS_PAD_P$75") (pintype "bidirectional"))
      (node (ref "U$1") (pin "P$76") (pinfunction "VSS_PAD_P$76") (pintype "bidirectional"))
      (node (ref "U$1") (pin "P$77") (pinfunction "VSS_PAD_P$77") (pintype "bidirectional"))
      (node (ref "U$1") (pin "P$78") (pinfunction "VSS_PAD_P$78") (pintype "bidirectional"))
      (node (ref "U$1") (pin "P$79") (pinfunction "VSS_PAD_P$79") (pintype "bidirectional"))
      (node (ref "U$1") (pin "P$80") (pinfunction "VSS_PAD_P$80") (pintype "bidirectional"))
      (node (ref "U$1") (pin "P$81") (pinfunction "VSS_PAD_P$81") (pintype "bidirectional"))
      (node (ref "U$1") (pin "P$82") (pinfunction "VSS_PAD_P$82") (pintype "bidirectional"))
      (node (ref "U$1") (pin "P$83") (pinfunction "VSS_PAD_P$83") (pintype "bidirectional"))
      (node (ref "U$1") (pin "P$84") (pinfunction "VSS_PAD_P$84") (pintype "bidirectional"))
      (node (ref "U$1") (pin "P$85") (pinfunction "VSS_PAD_P$85") (pintype "bidirectional"))
      (node (ref "U$1") (pin "P$86") (pinfunction "VSS_PAD_P$86") (pintype "bidirectional"))
      (node (ref "U$1") (pin "P$87") (pinfunction "VSS_PAD_P$87") (pintype "bidirectional"))
      (node (ref "U$1") (pin "P$88") (pinfunction "VSS_PAD_P$88") (pintype "bidirectional"))
      (node (ref "U$1") (pin "P$89") (pinfunction "VSS_PAD_P$89") (pintype "bidirectional"))
      (node (ref "U$1") (pin "P$90") (pinfunction "VSS_PAD_P$90") (pintype "bidirectional"))
      (node (ref "U$1") (pin "P$B7") (pinfunction "VSS_P$B7") (pintype "power_in"))
      (node (ref "U$1") (pin "P$F23") (pinfunction "VSS_PA_P$F23") (pintype "bidirectional"))
      (node (ref "U1") (pin "1") (pinfunction "CTG_1") (pintype "power_in"))
      (node (ref "U1") (pin "4") (pinfunction "GND_4") (pintype "power_in"))
      (node (ref "U1") (pin "6") (pinfunction "QSTRT_6") (pintype "input"))
      (node (ref "U1") (pin "9") (pinfunction "EP_9") (pintype "power_in"))
      (node (ref "X1") (pin "2") (pinfunction "2_2") (pintype "passive"))
      (node (ref "X1") (pin "4") (pinfunction "4_4") (pintype "passive"))
    )
    (net (code "16") (name "HAPTIC_EN") (class "Default")
      (node (ref "IC3") (pin "A1") (pinfunction "EN_A1") (pintype "bidirectional"))
      (node (ref "U$1") (pin "P$U1") (pinfunction "P0.12_P$U1") (pintype "bidirectional"))
    )
    (net (code "17") (name "IMU_INT1") (class "Default")
      (node (ref "IC2") (pin "5") (pinfunction "INT1_5") (pintype "bidirectional"))
      (node (ref "U$1") (pin "P$N1") (pinfunction "P0.08_P$N1") (pintype "bidirectional"))
    )
    (net (code "18") (name "IMU_INT2") (class "Default")
      (node (ref "IC2") (pin "6") (pinfunction "INT2_6") (pintype "bidirectional"))
      (node (ref "U$1") (pin "P$P2") (pinfunction "P1.08_P$P2") (pintype "bidirectional"))
    )
    (net (code "19") (name "LX1") (class "Default")
      (node (ref "IC9") (pin "B2") (pinfunction "SW1_1_B2") (pintype "bidirectional"))
      (node (ref "IC9") (pin "B3") (pinfunction "SW1_2_B3") (pintype "bidirectional"))
      (node (ref "L7") (pin "1") (pinfunction "1_1") (pintype "bidirectional"))
    )
    (net (code "20") (name "LX2") (class "Default")
      (node (ref "IC9") (pin "D2") (pinfunction "SW2_1_D2") (pintype "bidirectional"))
      (node (ref "IC9") (pin "D3") (pinfunction "SW2_2_D3") (pintype "bidirectional"))
      (node (ref "L7") (pin "2") (pinfunction "2_2") (pintype "bidirectional"))
    )
    (net (code "21") (name "MOSI") (class "Default")
      (node (ref "J2") (pin "14") (pinfunction "14_14") (pintype "bidirectional"))
      (node (ref "U$1") (pin "P$B13") (pinfunction "P0.03/AIN1_P$B13") (pintype "bidirectional"))
    )
    (net (code "22") (name "Net-(C6-Pad1)") (class "Default")
      (node (ref "C6") (pin "1") (pinfunction "1_1") (pintype "passive"))
      (node (ref "U$1") (pin "P$W1") (pinfunction "VDD_P$W1") (pintype "power_in"))
    )
    (net (code "23") (name "Net-(D2-K)") (class "Default")
      (node (ref "C2-EP-DR") (pin "1") (pinfunction "1_1") (pintype "passive"))
      (node (ref "D2") (pin "1") (pinfunction "K_1") (pintype "bidirectional"))
      (node (ref "D4") (pin "2") (pinfunction "A_2") (pintype "bidirectional"))
    )
    (net (code "24") (name "Net-(D5-A)") (class "Default")
      (node (ref "C2-EP-DR") (pin "2") (pinfunction "2_2") (pintype "passive"))
      (node (ref "D5") (pin "2") (pinfunction "A_2") (pintype "bidirectional"))
      (node (ref "L1") (pin "1") (pinfunction "1_1") (pintype "passive"))
      (node (ref "Q3") (pin "3") (pinfunction "D_3") (pintype "bidirectional"))
    )
    (net (code "25") (name "Net-(EPD_C1-Pad2)") (class "Default")
      (node (ref "EPD_C1") (pin "2") (pinfunction "2_2") (pintype "passive"))
      (node (ref "J2") (pin "5") (pinfunction "5_5") (pintype "bidirectional"))
    )
    (net (code "26") (name "Net-(EPD_C2-Pad2)") (class "Default")
      (node (ref "EPD_C2") (pin "2") (pinfunction "2_2") (pintype "passive"))
      (node (ref "J2") (pin "4") (pinfunction "4_4") (pintype "bidirectional"))
    )
    (net (code "27") (name "Net-(EPD_C6-Pad2)") (class "Default")
      (node (ref "EPD_C6") (pin "2") (pinfunction "2_2") (pintype "passive"))
      (node (ref "J2") (pin "18") (pinfunction "18_18") (pintype "bidirectional"))
    )
    (net (code "28") (name "Net-(EPD_C7-Pad2)") (class "Default")
      (node (ref "EPD_C7") (pin "2") (pinfunction "2_2") (pintype "passive"))
      (node (ref "J2") (pin "19") (pinfunction "19_19") (pintype "bidirectional"))
    )
    (net (code "29") (name "Net-(EPD_C8-Pad2)") (class "Default")
      (node (ref "EPD_C8") (pin "2") (pinfunction "2_2") (pintype "passive"))
      (node (ref "J2") (pin "20") (pinfunction "20_20") (pintype "bidirectional"))
    )
    (net (code "30") (name "Net-(EPD_C10-Pad2)") (class "Default")
      (node (ref "EPD_C10") (pin "2") (pinfunction "2_2") (pintype "passive"))
      (node (ref "J2") (pin "22") (pinfunction "22_22") (pintype "bidirectional"))
    )
    (net (code "31") (name "Net-(EPD_C12-Pad2)") (class "Default")
      (node (ref "EPD_C12") (pin "2") (pinfunction "2_2") (pintype "passive"))
      (node (ref "J2") (pin "24") (pinfunction "24_24") (pintype "bidirectional"))
    )
    (net (code "32") (name "Net-(IC1-TS{slash}MR)") (class "Default")
      (node (ref "IC1") (pin "D1") (pinfunction "TS/MR_D1") (pintype "bidirectional"))
      (node (ref "R1") (pin "1") (pinfunction "1_1") (pintype "bidirectional"))
    )
    (net (code "33") (name "Net-(IC2-CSB)") (class "Default")
      (node (ref "IC2") (pin "10") (pinfunction "CSB_10") (pintype "bidirectional"))
      (node (ref "IC2") (pin "7") (pinfunction "VDD_7") (pintype "bidirectional"))
    )
    (net (code "34") (name "Net-(IC2-SDO)") (class "Default")
      (node (ref "IC2") (pin "1") (pinfunction "SDO_1") (pintype "bidirectional"))
      (node (ref "R3") (pin "1") (pinfunction "1_1") (pintype "bidirectional"))
    )
    (net (code "35") (name "Net-(IC3-REG)") (class "Default")
      (node (ref "C32") (pin "2") (pinfunction "2_2") (pintype "passive"))
      (node (ref "IC3") (pin "A2") (pinfunction "REG_A2") (pintype "bidirectional"))
    )
    (net (code "36") (name "Net-(IC9-SCL)") (class "Default")
      (node (ref "IC9") (pin "D1") (pinfunction "SCL_D1") (pintype "bidirectional"))
      (node (ref "R4") (pin "1") (pinfunction "1_1") (pintype "bidirectional"))
    )
    (net (code "37") (name "Net-(IC9-SDA)") (class "Default")
      (node (ref "IC9") (pin "E1") (pinfunction "SDA_E1") (pintype "bidirectional"))
      (node (ref "R2") (pin "1") (pinfunction "1_1") (pintype "bidirectional"))
    )
    (net (code "38") (name "Net-(J3-CC1)") (class "Default")
      (node (ref "J3") (pin "A5") (pinfunction "CC1_A5") (pintype "bidirectional"))
      (node (ref "R1_USB") (pin "1") (pinfunction "1_1") (pintype "bidirectional"))
    )
    (net (code "39") (name "Net-(J3-CC2)") (class "Default")
      (node (ref "J3") (pin "B5") (pinfunction "CC2_B5") (pintype "bidirectional"))
      (node (ref "R2_USB") (pin "1") (pinfunction "1_1") (pintype "bidirectional"))
    )
    (net (code "40") (name "Net-(L2-Pad1)") (class "Default")
      (node (ref "L2") (pin "1") (pinfunction "1_1") (pintype "passive"))
      (node (ref "L3") (pin "2") (pinfunction "2_2") (pintype "passive"))
    )
    (net (code "41") (name "Net-(R1_EP_DR-Pad1)") (class "Default")
      (node (ref "R1_EP_DR") (pin "1") (pinfunction "1_1") (pintype "bidirectional"))
      (node (ref "R_TYPE_SEL") (pin "2") (pinfunction "2_2") (pintype "bidirectional"))
      (node (ref "SJ1") (pin "2") (pinfunction "2_2") (pintype "passive"))
    )
    (net (code "42") (name "Net-(U$1-ANT)") (class "Default")
      (node (ref "C3") (pin "1") (pinfunction "1_1") (pintype "passive"))
      (node (ref "U$1") (pin "P$H23") (pinfunction "ANT_P$H23") (pintype "bidirectional"))
      (node (ref "U$5") (pin "1") (pinfunction "1_1") (pintype "passive"))
    )
    (net (code "43") (name "Net-(U$1-DCC)") (class "Default")
      (node (ref "L2") (pin "2") (pinfunction "2_2") (pintype "passive"))
      (node (ref "U$1") (pin "P$B3") (pinfunction "DCC_P$B3") (pintype "output"))
    )
    (net (code "44") (name "Net-(U$1-DEC2)") (class "Default")
      (node (ref "C13") (pin "1") (pinfunction "1_1") (pintype "passive"))
      (node (ref "U$1") (pin "P$A18") (pinfunction "DEC2_P$A18") (pintype "bidirectional"))
    )
    (net (code "45") (name "Net-(U$1-DEC3)") (class "Default")
      (node (ref "C11") (pin "1") (pinfunction "1_1") (pintype "passive"))
      (node (ref "U$1") (pin "P$D23") (pinfunction "DEC3_P$D23") (pintype "bidirectional"))
    )
    (net (code "46") (name "Net-(U$1-DEC3V3)") (class "Default")
      (node (ref "C20") (pin "1") (pinfunction "1_1") (pintype "passive"))
      (node (ref "U$1") (pin "P$AC5") (pinfunction "DEC3V3_P$AC5") (pintype "bidirectional"))
    )
    (net (code "47") (name "Net-(U$1-DEC5)") (class "Default")
      (node (ref "C9") (pin "1") (pinfunction "1_1") (pintype "passive"))
      (node (ref "U$1") (pin "P$N24") (pinfunction "DEC5_P$N24") (pintype "bidirectional"))
    )
    (net (code "48") (name "Net-(U$1-XC1)") (class "Default")
      (node (ref "C1") (pin "1") (pinfunction "1_1") (pintype "passive"))
      (node (ref "U$1") (pin "P$B24") (pinfunction "XC1_P$B24") (pintype "input"))
      (node (ref "X1") (pin "1") (pinfunction "1_1") (pintype "passive"))
    )
    (net (code "49") (name "Net-(U$1-XC2)") (class "Default")
      (node (ref "C2") (pin "1") (pinfunction "1_1") (pintype "passive"))
      (node (ref "U$1") (pin "P$A23") (pinfunction "XC2_P$A23") (pintype "output"))
      (node (ref "X1") (pin "3") (pinfunction "3_3") (pintype "passive"))
    )
    (net (code "50") (name "OUT+") (class "Default")
      (node (ref "IC3") (pin "A3") (pinfunction "OUT+_A3") (pintype "bidirectional"))
      (node (ref "TP_OP") (pin "TP") (pinfunction "TP_TP") (pintype "input"))
    )
    (net (code "51") (name "OUT-") (class "Default")
      (node (ref "IC3") (pin "C3") (pinfunction "OUT-_C3") (pintype "bidirectional"))
      (node (ref "TP_ON") (pin "TP") (pinfunction "TP_TP") (pintype "input"))
    )
    (net (code "52") (name "P0.00{slash}XL1") (class "Default")
      (node (ref "C17") (pin "1") (pinfunction "1_1") (pintype "passive"))
      (node (ref "U$1") (pin "P$D2") (pinfunction "P0.00/XL1_P$D2") (pintype "bidirectional"))
      (node (ref "X2") (pin "2") (pinfunction "2_2") (pintype "passive"))
    )
    (net (code "53") (name "P0.01{slash}XL2") (class "Default")
      (node (ref "C18") (pin "1") (pinfunction "1_1") (pintype "passive"))
      (node (ref "U$1") (pin "P$F2") (pinfunction "P0.01/XL2_P$F2") (pintype "bidirectional"))
      (node (ref "X2") (pin "1") (pinfunction "1_1") (pintype "passive"))
    )
    (net (code "54") (name "P0.04") (class "Default")
      (node (ref "U$1") (pin "P$J1") (pinfunction "P0.04/AIN2_P$J1") (pintype "bidirectional"))
    )
    (net (code "55") (name "P0.09") (class "Default")
      (node (ref "U$1") (pin "P$L24") (pinfunction "P0.09/NFC1_P$L24") (pintype "bidirectional"))
    )
    (net (code "56") (name "P0.13") (class "Default")
      (node (ref "C30") (pin "2") (pinfunction "2_2") (pintype "passive"))
      (node (ref "R5") (pin "1") (pinfunction "1_1") (pintype "bidirectional"))
      (node (ref "SW_UP") (pin "2") (pinfunction "2_2") (pintype "passive"))
      (node (ref "U$1") (pin "P$AD8") (pinfunction "P0.13_P$AD8") (pintype "bidirectional"))
    )
    (net (code "57") (name "P0.14") (class "Default")
      (node (ref "C31") (pin "2") (pinfunction "2_2") (pintype "passive"))
      (node (ref "R8") (pin "1") (pinfunction "1_1") (pintype "bidirectional"))
      (node (ref "SW_ENT") (pin "2") (pinfunction "2_2") (pintype "passive"))
      (node (ref "U$1") (pin "P$AC9") (pinfunction "P0.14_P$AC9") (pintype "bidirectional"))
    )
    (net (code "58") (name "P0.19") (class "Default")
      (node (ref "U$1") (pin "P$AC15") (pinfunction "P0.19_P$AC15") (pintype "bidirectional"))
    )
    (net (code "59") (name "P0.20") (class "Default")
      (node (ref "U$1") (pin "P$AD16") (pinfunction "P0.20_P$AD16") (pintype "bidirectional"))
    )
    (net (code "60") (name "P0.21") (class "Default")
      (node (ref "U$1") (pin "P$AC17") (pinfunction "P0.21_P$AC17") (pintype "bidirectional"))
    )
    (net (code "61") (name "P0.22") (class "Default")
      (node (ref "U$1") (pin "P$AD18") (pinfunction "P0.22_P$AD18") (pintype "bidirectional"))
    )
    (net (code "62") (name "P0.23") (class "Default")
      (node (ref "U$1") (pin "P$AC19") (pinfunction "P0.23_P$AC19") (pintype "bidirectional"))
    )
    (net (code "63") (name "P0.24") (class "Default")
      (node (ref "U$1") (pin "P$AD20") (pinfunction "P0.24_P$AD20") (pintype "bidirectional"))
    )
    (net (code "64") (name "P0.25") (class "Default")
      (node (ref "U$1") (pin "P$AC21") (pinfunction "P0.25_P$AC21") (pintype "bidirectional"))
    )
    (net (code "65") (name "P0.26") (class "Default")
      (node (ref "U$1") (pin "P$G1") (pinfunction "P0.26_P$G1") (pintype "bidirectional"))
    )
    (net (code "66") (name "P0.27") (class "Default")
      (node (ref "U$1") (pin "P$H2") (pinfunction "P0.27_P$H2") (pintype "bidirectional"))
    )
    (net (code "67") (name "P0.28") (class "Default")
      (node (ref "U$1") (pin "P$B11") (pinfunction "P0.28/AIN4_P$B11") (pintype "bidirectional"))
    )
    (net (code "68") (name "P0.29") (class "Default")
      (node (ref "U$1") (pin "P$A10") (pinfunction "P0.29/AIN5_P$A10") (pintype "bidirectional"))
    )
    (net (code "69") (name "P0.30") (class "Default")
      (node (ref "U$1") (pin "P$B9") (pinfunction "P0.30/AIN6_P$B9") (pintype "bidirectional"))
    )
    (net (code "70") (name "P0.31") (class "Default")
      (node (ref "U$1") (pin "P$A8") (pinfunction "P0.31/AIN7_P$A8") (pintype "bidirectional"))
    )
    (net (code "71") (name "P1.01") (class "Default")
      (node (ref "Q1") (pin "1") (pinfunction "G_1") (pintype "bidirectional"))
      (node (ref "R_PWR_EPD") (pin "1") (pinfunction "1_1") (pintype "bidirectional"))
      (node (ref "U$1") (pin "P$Y23") (pinfunction "P1.01_P$Y23") (pintype "bidirectional"))
    )
    (net (code "72") (name "P1.02") (class "Default")
      (node (ref "C29") (pin "2") (pinfunction "2_2") (pintype "passive"))
      (node (ref "R7") (pin "1") (pinfunction "1_1") (pintype "bidirectional"))
      (node (ref "SW_DN") (pin "2") (pinfunction "2_2") (pintype "passive"))
      (node (ref "U$1") (pin "P$W24") (pinfunction "P1.02_P$W24") (pintype "bidirectional"))
    )
    (net (code "73") (name "P1.03") (class "Default")
      (node (ref "U$1") (pin "P$V23") (pinfunction "P1.03_P$V23") (pintype "bidirectional"))
    )
    (net (code "74") (name "P1.04") (class "Default")
      (node (ref "U$1") (pin "P$U24") (pinfunction "P1.04_P$U24") (pintype "bidirectional"))
    )
    (net (code "75") (name "P1.05") (class "Default")
      (node (ref "U$1") (pin "P$T23") (pinfunction "P1.05_P$T23") (pintype "bidirectional"))
    )
    (net (code "76") (name "P1.06") (class "Default")
      (node (ref "U$1") (pin "P$R24") (pinfunction "P1.06_P$R24") (pintype "bidirectional"))
    )
    (net (code "77") (name "P1.07") (class "Default")
      (node (ref "U$1") (pin "P$P23") (pinfunction "P1.07_P$P23") (pintype "bidirectional"))
    )
    (net (code "78") (name "P1.09") (class "Default")
      (node (ref "U$1") (pin "P$R1") (pinfunction "P1.09_P$R1") (pintype "bidirectional"))
    )
    (net (code "79") (name "P1.10") (class "Default")
      (node (ref "U$1") (pin "P$A20") (pinfunction "P1.10_P$A20") (pintype "bidirectional"))
    )
    (net (code "80") (name "P1.11") (class "Default")
      (node (ref "U$1") (pin "P$B19") (pinfunction "P1.11_P$B19") (pintype "bidirectional"))
    )
    (net (code "81") (name "P1.12") (class "Default")
      (node (ref "U$1") (pin "P$B17") (pinfunction "P1.12_P$B17") (pintype "bidirectional"))
    )
    (net (code "82") (name "P1.13") (class "Default")
      (node (ref "U$1") (pin "P$A16") (pinfunction "P1.13_P$A16") (pintype "bidirectional"))
    )
    (net (code "83") (name "P1.14") (class "Default")
      (node (ref "U$1") (pin "P$B15") (pinfunction "P1.14_P$B15") (pintype "bidirectional"))
    )
    (net (code "84") (name "P1.15") (class "Default")
      (node (ref "U$1") (pin "P$A14") (pinfunction "P1.15_P$A14") (pintype "bidirectional"))
    )
    (net (code "85") (name "PMIC_INT") (class "Default")
      (node (ref "IC1") (pin "A1") (pinfunction "~{INT}_A1") (pintype "bidirectional"))
      (node (ref "U$1") (pin "P$T2") (pinfunction "P0.11_P$T2") (pintype "bidirectional"))
    )
    (net (code "86") (name "PREVGH") (class "Default")
      (node (ref "D5") (pin "1") (pinfunction "K_1") (pintype "bidirectional"))
      (node (ref "EPD_C9") (pin "2") (pinfunction "2_2") (pintype "passive"))
      (node (ref "J2") (pin "21") (pinfunction "21_21") (pintype "bidirectional"))
    )
    (net (code "87") (name "PREVGL") (class "Default")
      (node (ref "D2") (pin "2") (pinfunction "A_2") (pintype "bidirectional"))
      (node (ref "EPD_C11") (pin "2") (pinfunction "2_2") (pintype "passive"))
      (node (ref "J2") (pin "23") (pinfunction "23_23") (pintype "bidirectional"))
    )
    (net (code "88") (name "RESE") (class "Default")
      (node (ref "J2") (pin "3") (pinfunction "3_3") (pintype "bidirectional"))
      (node (ref "Q3") (pin "2") (pinfunction "S_2") (pintype "bidirectional"))
      (node (ref "R1_EP_DR") (pin "2") (pinfunction "2_2") (pintype "bidirectional"))
    )
    (net (code "89") (name "RESET") (class "Default")
      (node (ref "J1") (pin "6") (pinfunction "6_6") (pintype "bidirectional"))
      (node (ref "TP_RESET") (pin "TP") (pinfunction "TP_TP") (pintype "input"))
      (node (ref "U$1") (pin "P$AC13") (pinfunction "P0.18/RESET_P$AC13") (pintype "bidirectional"))
    )
    (net (code "90") (name "RF") (class "Default")
      (node (ref "ANT1") (pin "1") (pinfunction "FEED_1") (pintype "input"))
      (node (ref "C22") (pin "1") (pinfunction "1_1") (pintype "passive"))
      (node (ref "C4") (pin "1") (pinfunction "1_1") (pintype "passive"))
      (node (ref "U$5") (pin "2") (pinfunction "2_2") (pintype "passive"))
    )
    (net (code "91") (name "SCK") (class "Default")
      (node (ref "J2") (pin "13") (pinfunction "13_13") (pintype "bidirectional"))
      (node (ref "U$1") (pin "P$A12") (pinfunction "P0.02/AIN0_P$A12") (pintype "bidirectional"))
    )
    (net (code "92") (name "SCL") (class "Default")
      (node (ref "IC1") (pin "B1") (pinfunction "SCL_B1") (pintype "bidirectional"))
      (node (ref "IC2") (pin "12") (pinfunction "SCX_12") (pintype "bidirectional"))
      (node (ref "IC3") (pin "C1") (pinfunction "SCL_C1") (pintype "bidirectional"))
      (node (ref "R17") (pin "2") (pinfunction "2_2") (pintype "bidirectional"))
      (node (ref "R4") (pin "2") (pinfunction "2_2") (pintype "bidirectional"))
      (node (ref "TP_SCL") (pin "TP") (pinfunction "TP_TP") (pintype "input"))
      (node (ref "U$1") (pin "P$M2") (pinfunction "P0.07_P$M2") (pintype "bidirectional"))
      (node (ref "U1") (pin "7") (pinfunction "SCL_7") (pintype "input"))
    )
    (net (code "93") (name "SDA") (class "Default")
      (node (ref "IC1") (pin "C1") (pinfunction "SDA_C1") (pintype "bidirectional"))
      (node (ref "IC2") (pin "2") (pinfunction "SDX_2") (pintype "bidirectional"))
      (node (ref "IC3") (pin "B2") (pinfunction "SDA_B2") (pintype "bidirectional"))
      (node (ref "R18") (pin "2") (pinfunction "2_2") (pintype "bidirectional"))
      (node (ref "R2") (pin "2") (pinfunction "2_2") (pintype "bidirectional"))
      (node (ref "TP_SDA") (pin "TP") (pinfunction "TP_TP") (pintype "input"))
      (node (ref "U$1") (pin "P$L1") (pinfunction "P0.06_P$L1") (pintype "bidirectional"))
      (node (ref "U1") (pin "8") (pinfunction "SDA_8") (pintype "bidirectional"))
    )
    (net (code "94") (name "SWDCLK") (class "Default")
      (node (ref "J1") (pin "4") (pinfunction "4_4") (pintype "bidirectional"))
      (node (ref "TP_SWDCLK") (pin "TP") (pinfunction "TP_TP") (pintype "input"))
      (node (ref "U$1") (pin "P$AA24") (pinfunction "SWDCLK_P$AA24") (pintype "input"))
    )
    (net (code "95") (name "SWDIO") (class "Default")
      (node (ref "J1") (pin "2") (pinfunction "2_2") (pintype "bidirectional"))
      (node (ref "TP_SWDIO") (pin "TP") (pinfunction "TP_TP") (pintype "input"))
      (node (ref "U$1") (pin "P$AC24") (pinfunction "SWDIO_P$AC24") (pintype "bidirectional"))
    )
    (net (code "96") (name "SWO") (class "Default")
      (node (ref "TP_SWO") (pin "TP") (pinfunction "TP_TP") (pintype "input"))
      (node (ref "U$1") (pin "P$AD22") (pinfunction "P1.00_P$AD22") (pintype "bidirectional"))
    )
    (net (code "97") (name "VBAT") (class "Default")
      (node (ref "C27") (pin "2") (pinfunction "2_2") (pintype "passive"))
      (node (ref "C37") (pin "2") (pinfunction "2_2") (pintype "passive"))
      (node (ref "IC1") (pin "C2") (pinfunction "BAT_C2") (pintype "bidirectional"))
      (node (ref "TP_VBAT") (pin "TP") (pinfunction "TP_TP") (pintype "input"))
      (node (ref "U1") (pin "2") (pinfunction "CELL_2") (pintype "power_in"))
      (node (ref "U1") (pin "3") (pinfunction "VDD_3") (pintype "power_in"))
    )
    (net (code "98") (name "VBUS") (class "Default")
      (node (ref "C21") (pin "1") (pinfunction "1_1") (pintype "passive"))
      (node (ref "C38") (pin "1") (pinfunction "1_1") (pintype "passive"))
      (node (ref "C42") (pin "2") (pinfunction "2_2") (pintype "passive"))
      (node (ref "C43") (pin "2") (pinfunction "2_2") (pintype "passive"))
      (node (ref "D1") (pin "5") (pinfunction "VBUS_5") (pintype "bidirectional"))
      (node (ref "IC1") (pin "A2") (pinfunction "IN_A2") (pintype "bidirectional"))
      (node (ref "J3") (pin "A4_B9") (pinfunction "VBUS_A4_B9") (pintype "power_in"))
      (node (ref "J3") (pin "A9_B4") (pinfunction "VBUS_A9_B4") (pintype "power_in"))
      (node (ref "U$1") (pin "P$AD2") (pinfunction "VBUS_P$AD2") (pintype "power_in"))
    )
    (net (code "99") (name "VREG") (class "Default")
      (node (ref "C23") (pin "1") (pinfunction "1_1") (pintype "passive"))
      (node (ref "C24") (pin "2") (pinfunction "2_2") (pintype "passive"))
      (node (ref "C39") (pin "1") (pinfunction "1_1") (pintype "passive"))
      (node (ref "IC1") (pin "B2") (pinfunction "SYS_B2") (pintype "bidirectional"))
      (node (ref "IC9") (pin "A1") (pinfunction "EN_A1") (pintype "bidirectional"))
      (node (ref "IC9") (pin "A2") (pinfunction "VIN_1_A2") (pintype "bidirectional"))
      (node (ref "IC9") (pin "A3") (pinfunction "VIN_2_A3") (pintype "bidirectional"))
      (node (ref "TP_VREG") (pin "TP") (pinfunction "TP_TP") (pintype "input"))
    )
    (net (code "100") (name "unconnected-(ANT1-NC-Pad2)") (class "Default")
      (node (ref "ANT1") (pin "2") (pinfunction "NC_2") (pintype "no_connect"))
    )
    (net (code "101") (name "unconnected-(IC2-ASCL-Pad11)") (class "Default")
      (node (ref "IC2") (pin "11") (pinfunction "ASCL_11") (pintype "bidirectional"))
    )
    (net (code "102") (name "unconnected-(IC2-ASDA-Pad4)") (class "Default")
      (node (ref "IC2") (pin "4") (pinfunction "ASDA_4") (pintype "bidirectional"))
    )
    (net (code "103") (name "unconnected-(IC9-AGND-PadC1)") (class "Default")
      (node (ref "IC9") (pin "C1") (pinfunction "AGND_C1") (pintype "bidirectional"))
    )
    (net (code "104") (name "unconnected-(IC9-VOUT_1-PadE2)") (class "Default")
      (node (ref "IC9") (pin "E2") (pinfunction "VOUT_1_E2") (pintype "bidirectional"))
    )
    (net (code "105") (name "unconnected-(J2-Pad1)") (class "Default")
      (node (ref "J2") (pin "1") (pinfunction "1_1") (pintype "bidirectional"))
    )
    (net (code "106") (name "unconnected-(J2-Pad6)") (class "Default")
      (node (ref "J2") (pin "6") (pinfunction "6_6") (pintype "bidirectional"))
    )
    (net (code "107") (name "unconnected-(J2-Pad7)") (class "Default")
      (node (ref "J2") (pin "7") (pinfunction "7_7") (pintype "bidirectional"))
    )
    (net (code "108") (name "unconnected-(J3-SBU1-PadA8)") (class "Default")
      (node (ref "J3") (pin "A8") (pinfunction "SBU1_A8") (pintype "bidirectional"))
    )
    (net (code "109") (name "unconnected-(J3-SBU2-PadB8)") (class "Default")
      (node (ref "J3") (pin "B8") (pinfunction "SBU2_B8") (pintype "bidirectional"))
    )
    (net (code "110") (name "unconnected-(U$1-DCCH-PadP$AB2)") (class "Default")
      (node (ref "U$1") (pin "P$AB2") (pinfunction "DCCH_P$AB2") (pintype "bidirectional"))
    )
    (net (code "111") (name "unconnected-(U$1-VDDH-PadP$Y2)") (class "Default")
      (node (ref "U$1") (pin "P$Y2") (pinfunction "VDDH_P$Y2") (pintype "power_in"))
    )
  )
)
